# SMS_with_FM_to_Genesis.net
KiCad netlist of a schematic drawn in EAGLE
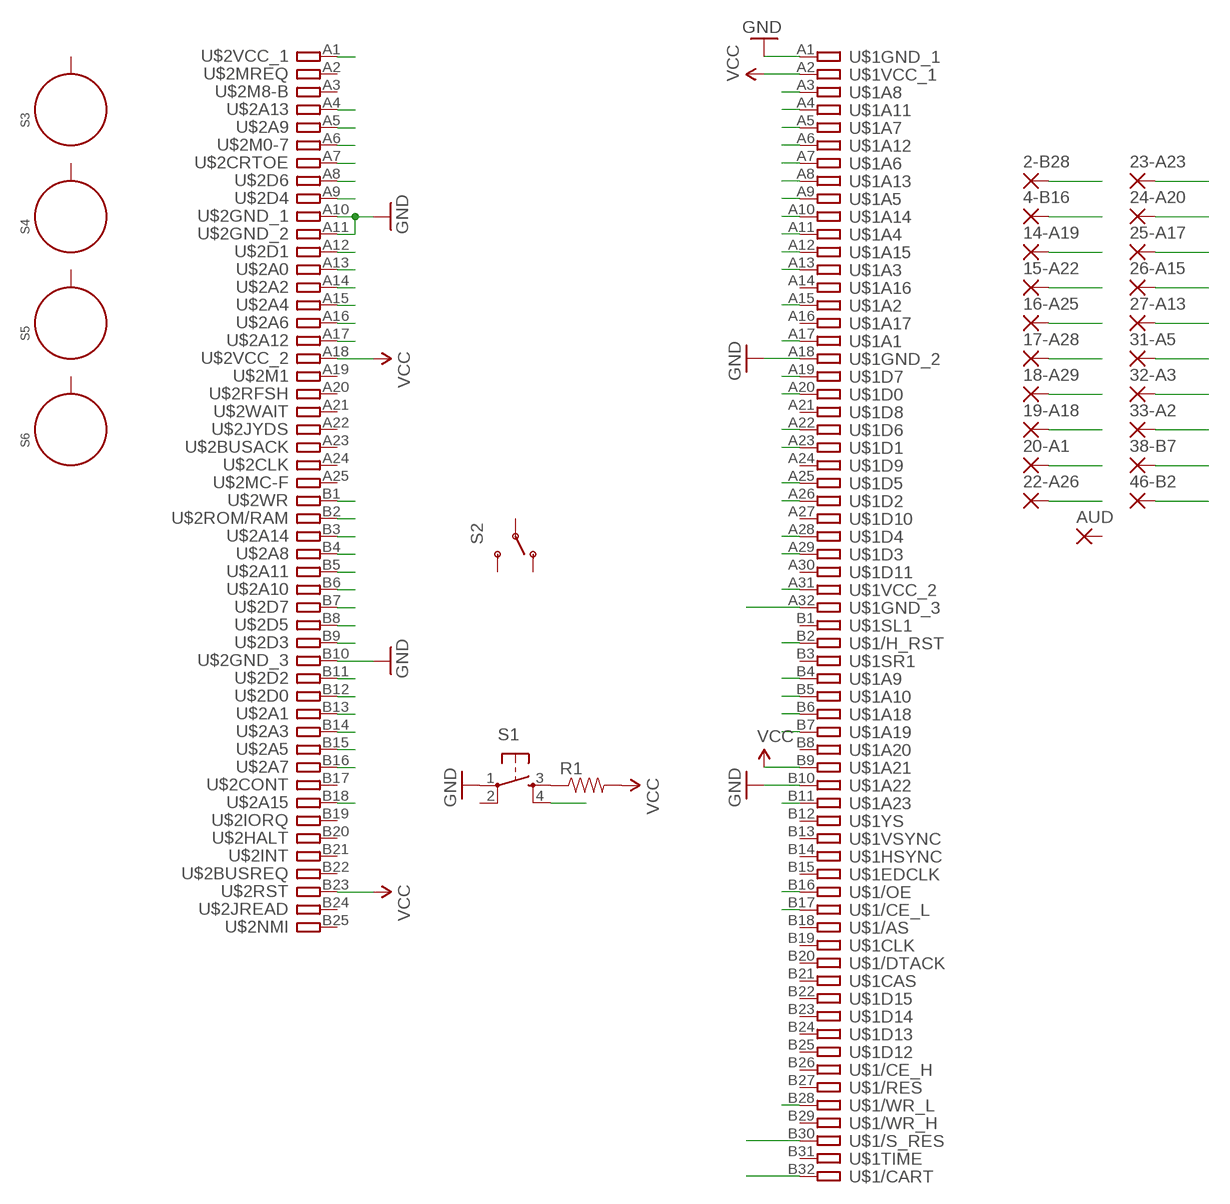
[diagram p0: schematic, sheet 1]

(export (version "E")
  (design (tool "Eeschema 10.0.6"))
  (components
    (comp (ref "2-B28")
      (value "WIREPADSMD1,27-254")
      (footprint "eagle-import:SMD1,27-2,54")
      (libsource (lib "eagle-import") (part "WIREPADSMD1,27-254"))
    )
    (comp (ref "4-B16")
      (value "WIREPADSMD1,27-254")
      (footprint "eagle-import:SMD1,27-2,54")
      (libsource (lib "eagle-import") (part "WIREPADSMD1,27-254"))
    )
    (comp (ref "14-A19")
      (value "WIREPADSMD1,27-254")
      (footprint "eagle-import:SMD1,27-2,54")
      (libsource (lib "eagle-import") (part "WIREPADSMD1,27-254"))
    )
    (comp (ref "15-A22")
      (value "WIREPADSMD1,27-254")
      (footprint "eagle-import:SMD1,27-2,54")
      (libsource (lib "eagle-import") (part "WIREPADSMD1,27-254"))
    )
    (comp (ref "16-A25")
      (value "WIREPADSMD1,27-254")
      (footprint "eagle-import:SMD1,27-2,54")
      (libsource (lib "eagle-import") (part "WIREPADSMD1,27-254"))
    )
    (comp (ref "17-A28")
      (value "WIREPADSMD1,27-254")
      (footprint "eagle-import:SMD1,27-2,54")
      (libsource (lib "eagle-import") (part "WIREPADSMD1,27-254"))
    )
    (comp (ref "18-A29")
      (value "WIREPADSMD1,27-254")
      (footprint "eagle-import:SMD1,27-2,54")
      (libsource (lib "eagle-import") (part "WIREPADSMD1,27-254"))
    )
    (comp (ref "19-A18")
      (value "WIREPADSMD1,27-254")
      (footprint "eagle-import:SMD1,27-2,54")
      (libsource (lib "eagle-import") (part "WIREPADSMD1,27-254"))
    )
    (comp (ref "20-A1")
      (value "WIREPADSMD1,27-254")
      (footprint "eagle-import:SMD1,27-2,54")
      (libsource (lib "eagle-import") (part "WIREPADSMD1,27-254"))
    )
    (comp (ref "22-A26")
      (value "WIREPADSMD1,27-254")
      (footprint "eagle-import:SMD1,27-2,54")
      (libsource (lib "eagle-import") (part "WIREPADSMD1,27-254"))
    )
    (comp (ref "23-A23")
      (value "WIREPADSMD1,27-254")
      (footprint "eagle-import:SMD1,27-2,54")
      (libsource (lib "eagle-import") (part "WIREPADSMD1,27-254"))
    )
    (comp (ref "24-A20")
      (value "WIREPADSMD1,27-254")
      (footprint "eagle-import:SMD1,27-2,54")
      (libsource (lib "eagle-import") (part "WIREPADSMD1,27-254"))
    )
    (comp (ref "25-A17")
      (value "WIREPADSMD1,27-254")
      (footprint "eagle-import:SMD1,27-2,54")
      (libsource (lib "eagle-import") (part "WIREPADSMD1,27-254"))
    )
    (comp (ref "26-A15")
      (value "WIREPADSMD1,27-254")
      (footprint "eagle-import:SMD1,27-2,54")
      (libsource (lib "eagle-import") (part "WIREPADSMD1,27-254"))
    )
    (comp (ref "27-A13")
      (value "WIREPADSMD1,27-254")
      (footprint "eagle-import:SMD1,27-2,54")
      (libsource (lib "eagle-import") (part "WIREPADSMD1,27-254"))
    )
    (comp (ref "31-A5")
      (value "WIREPADSMD1,27-254")
      (footprint "eagle-import:SMD1,27-2,54")
      (libsource (lib "eagle-import") (part "WIREPADSMD1,27-254"))
    )
    (comp (ref "32-A3")
      (value "WIREPADSMD1,27-254")
      (footprint "eagle-import:SMD1,27-2,54")
      (libsource (lib "eagle-import") (part "WIREPADSMD1,27-254"))
    )
    (comp (ref "33-A2")
      (value "WIREPADSMD1,27-254")
      (footprint "eagle-import:SMD1,27-2,54")
      (libsource (lib "eagle-import") (part "WIREPADSMD1,27-254"))
    )
    (comp (ref "38-B7")
      (value "WIREPADSMD1,27-254")
      (footprint "eagle-import:SMD1,27-2,54")
      (libsource (lib "eagle-import") (part "WIREPADSMD1,27-254"))
    )
    (comp (ref "46-B2")
      (value "WIREPADSMD1,27-254")
      (footprint "eagle-import:SMD1,27-2,54")
      (libsource (lib "eagle-import") (part "WIREPADSMD1,27-254"))
    )
    (comp (ref "AUD")
      (value "WIREPADSMD1,27-254")
      (footprint "eagle-import:SMD1,27-2,54")
      (libsource (lib "eagle-import") (part "WIREPADSMD1,27-254"))
    )
    (comp (ref "R1")
      (value "RESISTOR0805-RES")
      (footprint "eagle-import:0805")
      (libsource (lib "eagle-import") (part "RESISTOR0805-RES"))
    )
    (comp (ref "S1")
      (value "TAC_SWITCHSMD")
      (footprint "eagle-import:TACTILE-SWITCH-SMD")
      (libsource (lib "eagle-import") (part "TAC_SWITCHSMD"))
    )
    (comp (ref "S2")
      (value "SWITCH-SPDTPTH")
      (footprint "eagle-import:SWITCH-SPDT")
      (libsource (lib "eagle-import") (part "SWITCH-SPDTPTH"))
    )
    (comp (ref "S3")
      (value "STANDOFF_ELECTRICAL")
      (footprint "eagle-import:STANDOFF-ELECTRICAL")
      (libsource (lib "eagle-import") (part "STANDOFF_ELECTRICAL"))
    )
    (comp (ref "S4")
      (value "STANDOFF_ELECTRICAL")
      (footprint "eagle-import:STANDOFF-ELECTRICAL")
      (libsource (lib "eagle-import") (part "STANDOFF_ELECTRICAL"))
    )
    (comp (ref "S5")
      (value "STANDOFF_ELECTRICAL")
      (footprint "eagle-import:STANDOFF-ELECTRICAL")
      (libsource (lib "eagle-import") (part "STANDOFF_ELECTRICAL"))
    )
    (comp (ref "S6")
      (value "STANDOFF_ELECTRICAL")
      (footprint "eagle-import:STANDOFF-ELECTRICAL")
      (libsource (lib "eagle-import") (part "STANDOFF_ELECTRICAL"))
    )
    (comp (ref "U$1")
      (value "GENESIS-LARGE")
      (footprint "eagle-import:GENESIS-LARGE")
      (libsource (lib "eagle-import") (part "GENESIS-LARGE"))
    )
    (comp (ref "U$2")
      (value "SMS-R")
      (footprint "eagle-import:SMS")
      (libsource (lib "eagle-import") (part "SMS-R"))
    )
  )
  (nets
    (net (code "1") (name "/A3") (class "Default")
      (node (ref "32-A3") (pin "1") (pinfunction "P_1") (pintype "passive"))
      (node (ref "U$1") (pin "A3") (pinfunction "P_A3") (pintype "bidirectional"))
      (node (ref "U$2") (pin "B16") (pinfunction "P_B16") (pintype "passive"))
    )
    (net (code "2") (name "/A4") (class "Default")
      (node (ref "U$1") (pin "A4") (pinfunction "P_A4") (pintype "bidirectional"))
      (node (ref "U$2") (pin "B6") (pinfunction "P_B6") (pintype "passive"))
    )
    (net (code "3") (name "/A5") (class "Default")
      (node (ref "31-A5") (pin "1") (pinfunction "P_1") (pintype "passive"))
      (node (ref "U$1") (pin "A5") (pinfunction "P_A5") (pintype "bidirectional"))
      (node (ref "U$2") (pin "A16") (pinfunction "P_A16") (pintype "passive"))
    )
    (net (code "4") (name "/A6") (class "Default")
      (node (ref "U$1") (pin "A6") (pinfunction "P_A6") (pintype "bidirectional"))
      (node (ref "U$2") (pin "B5") (pinfunction "P_B5") (pintype "passive"))
    )
    (net (code "5") (name "/A7") (class "Default")
      (node (ref "U$1") (pin "A7") (pinfunction "P_A7") (pintype "bidirectional"))
      (node (ref "U$2") (pin "B15") (pinfunction "P_B15") (pintype "passive"))
    )
    (net (code "6") (name "/A8") (class "Default")
      (node (ref "U$1") (pin "A8") (pinfunction "P_A8") (pintype "bidirectional"))
      (node (ref "U$2") (pin "A17") (pinfunction "P_A17") (pintype "passive"))
    )
    (net (code "7") (name "/A9") (class "Default")
      (node (ref "U$1") (pin "A9") (pinfunction "P_A9") (pintype "bidirectional"))
      (node (ref "U$2") (pin "A15") (pinfunction "P_A15") (pintype "passive"))
    )
    (net (code "8") (name "/A10") (class "Default")
      (node (ref "U$1") (pin "A10") (pinfunction "P_A10") (pintype "bidirectional"))
      (node (ref "U$2") (pin "A4") (pinfunction "P_A4") (pintype "passive"))
    )
    (net (code "9") (name "/A11") (class "Default")
      (node (ref "U$1") (pin "A11") (pinfunction "P_A11") (pintype "bidirectional"))
      (node (ref "U$2") (pin "B14") (pinfunction "P_B14") (pintype "passive"))
    )
    (net (code "10") (name "/A12") (class "Default")
      (node (ref "U$1") (pin "A12") (pinfunction "P_A12") (pintype "bidirectional"))
      (node (ref "U$2") (pin "B3") (pinfunction "P_B3") (pintype "passive"))
    )
    (net (code "11") (name "/A13") (class "Default")
      (node (ref "27-A13") (pin "1") (pinfunction "P_1") (pintype "passive"))
      (node (ref "U$1") (pin "A13") (pinfunction "P_A13") (pintype "bidirectional"))
      (node (ref "U$2") (pin "A14") (pinfunction "P_A14") (pintype "passive"))
    )
    (net (code "12") (name "/A15") (class "Default")
      (node (ref "26-A15") (pin "1") (pinfunction "P_1") (pintype "passive"))
      (node (ref "U$1") (pin "A15") (pinfunction "P_A15") (pintype "bidirectional"))
      (node (ref "U$2") (pin "B13") (pinfunction "P_B13") (pintype "passive"))
    )
    (net (code "13") (name "/A17") (class "Default")
      (node (ref "25-A17") (pin "1") (pinfunction "P_1") (pintype "passive"))
      (node (ref "U$1") (pin "A17") (pinfunction "P_A17") (pintype "bidirectional"))
      (node (ref "U$2") (pin "A13") (pinfunction "P_A13") (pintype "passive"))
    )
    (net (code "14") (name "/A19") (class "Default")
      (node (ref "14-A19") (pin "1") (pinfunction "P_1") (pintype "passive"))
      (node (ref "U$1") (pin "A19") (pinfunction "P_A19") (pintype "bidirectional"))
      (node (ref "U$2") (pin "B7") (pinfunction "P_B7") (pintype "passive"))
    )
    (net (code "15") (name "/A20") (class "Default")
      (node (ref "24-A20") (pin "1") (pinfunction "P_1") (pintype "passive"))
      (node (ref "U$1") (pin "A20") (pinfunction "P_A20") (pintype "bidirectional"))
      (node (ref "U$2") (pin "B12") (pinfunction "P_B12") (pintype "passive"))
    )
    (net (code "16") (name "/A22") (class "Default")
      (node (ref "15-A22") (pin "1") (pinfunction "P_1") (pintype "passive"))
      (node (ref "U$1") (pin "A22") (pinfunction "P_A22") (pintype "bidirectional"))
      (node (ref "U$2") (pin "A8") (pinfunction "P_A8") (pintype "passive"))
    )
    (net (code "17") (name "/A23") (class "Default")
      (node (ref "23-A23") (pin "1") (pinfunction "P_1") (pintype "passive"))
      (node (ref "U$1") (pin "A23") (pinfunction "P_A23") (pintype "bidirectional"))
      (node (ref "U$2") (pin "A12") (pinfunction "P_A12") (pintype "passive"))
    )
    (net (code "18") (name "/A25") (class "Default")
      (node (ref "16-A25") (pin "1") (pinfunction "P_1") (pintype "passive"))
      (node (ref "U$1") (pin "A25") (pinfunction "P_A25") (pintype "bidirectional"))
      (node (ref "U$2") (pin "B8") (pinfunction "P_B8") (pintype "passive"))
    )
    (net (code "19") (name "/A26") (class "Default")
      (node (ref "22-A26") (pin "1") (pinfunction "P_1") (pintype "passive"))
      (node (ref "U$1") (pin "A26") (pinfunction "P_A26") (pintype "bidirectional"))
      (node (ref "U$2") (pin "B11") (pinfunction "P_B11") (pintype "passive"))
    )
    (net (code "20") (name "/A28") (class "Default")
      (node (ref "17-A28") (pin "1") (pinfunction "P_1") (pintype "passive"))
      (node (ref "U$1") (pin "A28") (pinfunction "P_A28") (pintype "bidirectional"))
      (node (ref "U$2") (pin "A9") (pinfunction "P_A9") (pintype "passive"))
    )
    (net (code "21") (name "/A29") (class "Default")
      (node (ref "18-A29") (pin "1") (pinfunction "P_1") (pintype "passive"))
      (node (ref "U$1") (pin "A29") (pinfunction "P_A29") (pintype "bidirectional"))
      (node (ref "U$2") (pin "B9") (pinfunction "P_B9") (pintype "passive"))
    )
    (net (code "22") (name "/A31") (class "Default")
      (node (ref "U$1") (pin "A31") (pinfunction "P_A31") (pintype "bidirectional"))
      (node (ref "U$2") (pin "A1") (pinfunction "P_A1") (pintype "passive"))
    )
    (net (code "23") (name "/B2") (class "Default")
      (node (ref "46-B2") (pin "1") (pinfunction "P_1") (pintype "passive"))
      (node (ref "U$1") (pin "B2") (pinfunction "P_B2") (pintype "bidirectional"))
    )
    (net (code "24") (name "/B4") (class "Default")
      (node (ref "U$1") (pin "B4") (pinfunction "P_B4") (pintype "bidirectional"))
      (node (ref "U$2") (pin "B4") (pinfunction "P_B4") (pintype "passive"))
    )
    (net (code "25") (name "/B5") (class "Default")
      (node (ref "U$1") (pin "B5") (pinfunction "P_B5") (pintype "bidirectional"))
      (node (ref "U$2") (pin "A5") (pinfunction "P_A5") (pintype "passive"))
    )
    (net (code "26") (name "/B6") (class "Default")
      (node (ref "U$1") (pin "B6") (pinfunction "P_B6") (pintype "bidirectional"))
      (node (ref "U$2") (pin "A7") (pinfunction "P_A7") (pintype "passive"))
    )
    (net (code "27") (name "/B7") (class "Default")
      (node (ref "38-B7") (pin "1") (pinfunction "P_1") (pintype "passive"))
      (node (ref "U$1") (pin "B7") (pinfunction "P_B7") (pintype "bidirectional"))
    )
    (net (code "28") (name "/B11") (class "Default")
      (node (ref "S1") (pin "4") (pinfunction "4_4") (pintype "passive"))
      (node (ref "U$1") (pin "B11") (pinfunction "P_B11") (pintype "bidirectional"))
    )
    (net (code "29") (name "/B16") (class "Default")
      (node (ref "4-B16") (pin "1") (pinfunction "P_1") (pintype "passive"))
      (node (ref "U$1") (pin "B16") (pinfunction "P_B16") (pintype "bidirectional"))
      (node (ref "U$2") (pin "B2") (pinfunction "P_B2") (pintype "passive"))
    )
    (net (code "30") (name "/B17") (class "Default")
      (node (ref "U$1") (pin "B17") (pinfunction "P_B17") (pintype "bidirectional"))
      (node (ref "U$2") (pin "A6") (pinfunction "P_A6") (pintype "passive"))
      (node (ref "U$2") (pin "B18") (pinfunction "P_B18") (pintype "passive"))
    )
    (net (code "31") (name "/B28") (class "Default")
      (node (ref "2-B28") (pin "1") (pinfunction "P_1") (pintype "passive"))
      (node (ref "U$1") (pin "B28") (pinfunction "P_B28") (pintype "bidirectional"))
      (node (ref "U$2") (pin "B1") (pinfunction "P_B1") (pintype "passive"))
    )
    (net (code "32") (name "/SMS") (class "Default")
      (node (ref "U$1") (pin "A32") (pinfunction "P_A32") (pintype "bidirectional"))
      (node (ref "U$1") (pin "B30") (pinfunction "P_B30") (pintype "bidirectional"))
      (node (ref "U$1") (pin "B32") (pinfunction "P_B32") (pintype "bidirectional"))
    )
    (net (code "33") (name "GND") (class "Default")
      (node (ref "19-A18") (pin "1") (pinfunction "P_1") (pintype "passive"))
      (node (ref "20-A1") (pin "1") (pinfunction "P_1") (pintype "passive"))
      (node (ref "S1") (pin "1") (pinfunction "1_1") (pintype "passive"))
      (node (ref "U$1") (pin "A1") (pinfunction "P_A1") (pintype "bidirectional"))
      (node (ref "U$1") (pin "A18") (pinfunction "P_A18") (pintype "bidirectional"))
      (node (ref "U$1") (pin "B10") (pinfunction "P_B10") (pintype "bidirectional"))
      (node (ref "U$2") (pin "A10") (pinfunction "P_A10") (pintype "passive"))
      (node (ref "U$2") (pin "A11") (pinfunction "P_A11") (pintype "passive"))
      (node (ref "U$2") (pin "B10") (pinfunction "P_B10") (pintype "passive"))
    )
    (net (code "34") (name "Net-(R1-Pad1)") (class "Default")
      (node (ref "R1") (pin "1") (pinfunction "1_1") (pintype "passive"))
      (node (ref "S1") (pin "3") (pinfunction "3_3") (pintype "passive"))
    )
    (net (code "35") (name "VCC") (class "Default")
      (node (ref "33-A2") (pin "1") (pinfunction "P_1") (pintype "passive"))
      (node (ref "R1") (pin "2") (pinfunction "2_2") (pintype "passive"))
      (node (ref "U$1") (pin "A2") (pinfunction "P_A2") (pintype "bidirectional"))
      (node (ref "U$1") (pin "B9") (pinfunction "P_B9") (pintype "bidirectional"))
      (node (ref "U$2") (pin "A18") (pinfunction "P_A18") (pintype "passive"))
      (node (ref "U$2") (pin "B23") (pinfunction "P_B23") (pintype "passive"))
    )
    (net (code "36") (name "unconnected-(AUD-P-Pad1)") (class "Default")
      (node (ref "AUD") (pin "1") (pinfunction "P_1") (pintype "passive"))
    )
    (net (code "37") (name "unconnected-(S1-Pad2)") (class "Default")
      (node (ref "S1") (pin "2") (pinfunction "2_2") (pintype "passive"))
    )
    (net (code "38") (name "unconnected-(S2-O-Pad1)") (class "Default")
      (node (ref "S2") (pin "1") (pinfunction "O_1") (pintype "passive"))
    )
    (net (code "39") (name "unconnected-(S2-P-Pad2)") (class "Default")
      (node (ref "S2") (pin "2") (pinfunction "P_2") (pintype "passive"))
    )
    (net (code "40") (name "unconnected-(S2-S-Pad3)") (class "Default")
      (node (ref "S2") (pin "3") (pinfunction "S_3") (pintype "passive"))
    )
    (net (code "41") (name "unconnected-(S3-P$1-PadP1)") (class "Default")
      (node (ref "S3") (pin "P1") (pinfunction "P$1_P1") (pintype "bidirectional"))
    )
    (net (code "42") (name "unconnected-(S4-P$1-PadP1)") (class "Default")
      (node (ref "S4") (pin "P1") (pinfunction "P$1_P1") (pintype "bidirectional"))
    )
    (net (code "43") (name "unconnected-(S5-P$1-PadP1)") (class "Default")
      (node (ref "S5") (pin "P1") (pinfunction "P$1_P1") (pintype "bidirectional"))
    )
    (net (code "44") (name "unconnected-(S6-P$1-PadP1)") (class "Default")
      (node (ref "S6") (pin "P1") (pinfunction "P$1_P1") (pintype "bidirectional"))
    )
    (net (code "45") (name "unconnected-(U$1A-P-PadB18)") (class "Default")
      (node (ref "U$1") (pin "B18") (pinfunction "P_B18") (pintype "bidirectional"))
    )
    (net (code "46") (name "unconnected-(U$1AI-P-PadB21)") (class "Default")
      (node (ref "U$1") (pin "B21") (pinfunction "P_B21") (pintype "bidirectional"))
    )
    (net (code "47") (name "unconnected-(U$1AJ-P-PadB19)") (class "Default")
      (node (ref "U$1") (pin "B19") (pinfunction "P_B19") (pintype "bidirectional"))
    )
    (net (code "48") (name "unconnected-(U$1AM-P-PadA27)") (class "Default")
      (node (ref "U$1") (pin "A27") (pinfunction "P_A27") (pintype "bidirectional"))
    )
    (net (code "49") (name "unconnected-(U$1AN-P-PadA30)") (class "Default")
      (node (ref "U$1") (pin "A30") (pinfunction "P_A30") (pintype "bidirectional"))
    )
    (net (code "50") (name "unconnected-(U$1AO-P-PadB25)") (class "Default")
      (node (ref "U$1") (pin "B25") (pinfunction "P_B25") (pintype "bidirectional"))
    )
    (net (code "51") (name "unconnected-(U$1AP-P-PadB24)") (class "Default")
      (node (ref "U$1") (pin "B24") (pinfunction "P_B24") (pintype "bidirectional"))
    )
    (net (code "52") (name "unconnected-(U$1AQ-P-PadB23)") (class "Default")
      (node (ref "U$1") (pin "B23") (pinfunction "P_B23") (pintype "bidirectional"))
    )
    (net (code "53") (name "unconnected-(U$1AR-P-PadB22)") (class "Default")
      (node (ref "U$1") (pin "B22") (pinfunction "P_B22") (pintype "bidirectional"))
    )
    (net (code "54") (name "unconnected-(U$1AY-P-PadA21)") (class "Default")
      (node (ref "U$1") (pin "A21") (pinfunction "P_A21") (pintype "bidirectional"))
    )
    (net (code "55") (name "unconnected-(U$1AZ-P-PadA24)") (class "Default")
      (node (ref "U$1") (pin "A24") (pinfunction "P_A24") (pintype "bidirectional"))
    )
    (net (code "56") (name "unconnected-(U$1BA-P-PadB15)") (class "Default")
      (node (ref "U$1") (pin "B15") (pinfunction "P_B15") (pintype "bidirectional"))
    )
    (net (code "57") (name "unconnected-(U$1BE-P-PadB14)") (class "Default")
      (node (ref "U$1") (pin "B14") (pinfunction "P_B14") (pintype "bidirectional"))
    )
    (net (code "58") (name "unconnected-(U$1BF-P-PadB1)") (class "Default")
      (node (ref "U$1") (pin "B1") (pinfunction "P_B1") (pintype "bidirectional"))
    )
    (net (code "59") (name "unconnected-(U$1BG-P-PadB3)") (class "Default")
      (node (ref "U$1") (pin "B3") (pinfunction "P_B3") (pintype "bidirectional"))
    )
    (net (code "60") (name "unconnected-(U$1BH-P-PadB31)") (class "Default")
      (node (ref "U$1") (pin "B31") (pinfunction "P_B31") (pintype "bidirectional"))
    )
    (net (code "61") (name "unconnected-(U$1BK-P-PadB13)") (class "Default")
      (node (ref "U$1") (pin "B13") (pinfunction "P_B13") (pintype "bidirectional"))
    )
    (net (code "62") (name "unconnected-(U$1BL-P-PadB12)") (class "Default")
      (node (ref "U$1") (pin "B12") (pinfunction "P_B12") (pintype "bidirectional"))
    )
    (net (code "63") (name "unconnected-(U$1C-P-PadB26)") (class "Default")
      (node (ref "U$1") (pin "B26") (pinfunction "P_B26") (pintype "bidirectional"))
    )
    (net (code "64") (name "unconnected-(U$1E-P-PadB20)") (class "Default")
      (node (ref "U$1") (pin "B20") (pinfunction "P_B20") (pintype "bidirectional"))
    )
    (net (code "65") (name "unconnected-(U$1H-P-PadB27)") (class "Default")
      (node (ref "U$1") (pin "B27") (pinfunction "P_B27") (pintype "bidirectional"))
    )
    (net (code "66") (name "unconnected-(U$1J-P-PadB29)") (class "Default")
      (node (ref "U$1") (pin "B29") (pinfunction "P_B29") (pintype "bidirectional"))
    )
    (net (code "67") (name "unconnected-(U$1S-P-PadA14)") (class "Default")
      (node (ref "U$1") (pin "A14") (pinfunction "P_A14") (pintype "bidirectional"))
    )
    (net (code "68") (name "unconnected-(U$1T-P-PadA16)") (class "Default")
      (node (ref "U$1") (pin "A16") (pinfunction "P_A16") (pintype "bidirectional"))
    )
    (net (code "69") (name "unconnected-(U$1X-P-PadB8)") (class "Default")
      (node (ref "U$1") (pin "B8") (pinfunction "P_B8") (pintype "bidirectional"))
    )
    (net (code "70") (name "unconnected-(U$2AG-P-PadB20)") (class "Default")
      (node (ref "U$2") (pin "B20") (pinfunction "P_B20") (pintype "passive"))
    )
    (net (code "71") (name "unconnected-(U$2AH-P-PadB21)") (class "Default")
      (node (ref "U$2") (pin "B21") (pinfunction "P_B21") (pintype "passive"))
    )
    (net (code "72") (name "unconnected-(U$2AI-P-PadB19)") (class "Default")
      (node (ref "U$2") (pin "B19") (pinfunction "P_B19") (pintype "passive"))
    )
    (net (code "73") (name "unconnected-(U$2AJ-P-PadB24)") (class "Default")
      (node (ref "U$2") (pin "B24") (pinfunction "P_B24") (pintype "passive"))
    )
    (net (code "74") (name "unconnected-(U$2AK-P-PadA22)") (class "Default")
      (node (ref "U$2") (pin "A22") (pinfunction "P_A22") (pintype "passive"))
    )
    (net (code "75") (name "unconnected-(U$2AM-P-PadA19)") (class "Default")
      (node (ref "U$2") (pin "A19") (pinfunction "P_A19") (pintype "passive"))
    )
    (net (code "76") (name "unconnected-(U$2AN-P-PadA3)") (class "Default")
      (node (ref "U$2") (pin "A3") (pinfunction "P_A3") (pintype "passive"))
    )
    (net (code "77") (name "unconnected-(U$2AO-P-PadA25)") (class "Default")
      (node (ref "U$2") (pin "A25") (pinfunction "P_A25") (pintype "passive"))
    )
    (net (code "78") (name "unconnected-(U$2AP-P-PadA2)") (class "Default")
      (node (ref "U$2") (pin "A2") (pinfunction "P_A2") (pintype "passive"))
    )
    (net (code "79") (name "unconnected-(U$2AQ-P-PadB25)") (class "Default")
      (node (ref "U$2") (pin "B25") (pinfunction "P_B25") (pintype "passive"))
    )
    (net (code "80") (name "unconnected-(U$2AR-P-PadA20)") (class "Default")
      (node (ref "U$2") (pin "A20") (pinfunction "P_A20") (pintype "passive"))
    )
    (net (code "81") (name "unconnected-(U$2AW-P-PadA21)") (class "Default")
      (node (ref "U$2") (pin "A21") (pinfunction "P_A21") (pintype "passive"))
    )
    (net (code "82") (name "unconnected-(U$2Q-P-PadA23)") (class "Default")
      (node (ref "U$2") (pin "A23") (pinfunction "P_A23") (pintype "passive"))
    )
    (net (code "83") (name "unconnected-(U$2R-P-PadB22)") (class "Default")
      (node (ref "U$2") (pin "B22") (pinfunction "P_B22") (pintype "passive"))
    )
    (net (code "84") (name "unconnected-(U$2S-P-PadA24)") (class "Default")
      (node (ref "U$2") (pin "A24") (pinfunction "P_A24") (pintype "passive"))
    )
    (net (code "85") (name "unconnected-(U$2T-P-PadB17)") (class "Default")
      (node (ref "U$2") (pin "B17") (pinfunction "P_B17") (pintype "passive"))
    )
  )
)
